# 18650_Test.net
KiCad netlist of a schematic drawn in EAGLE
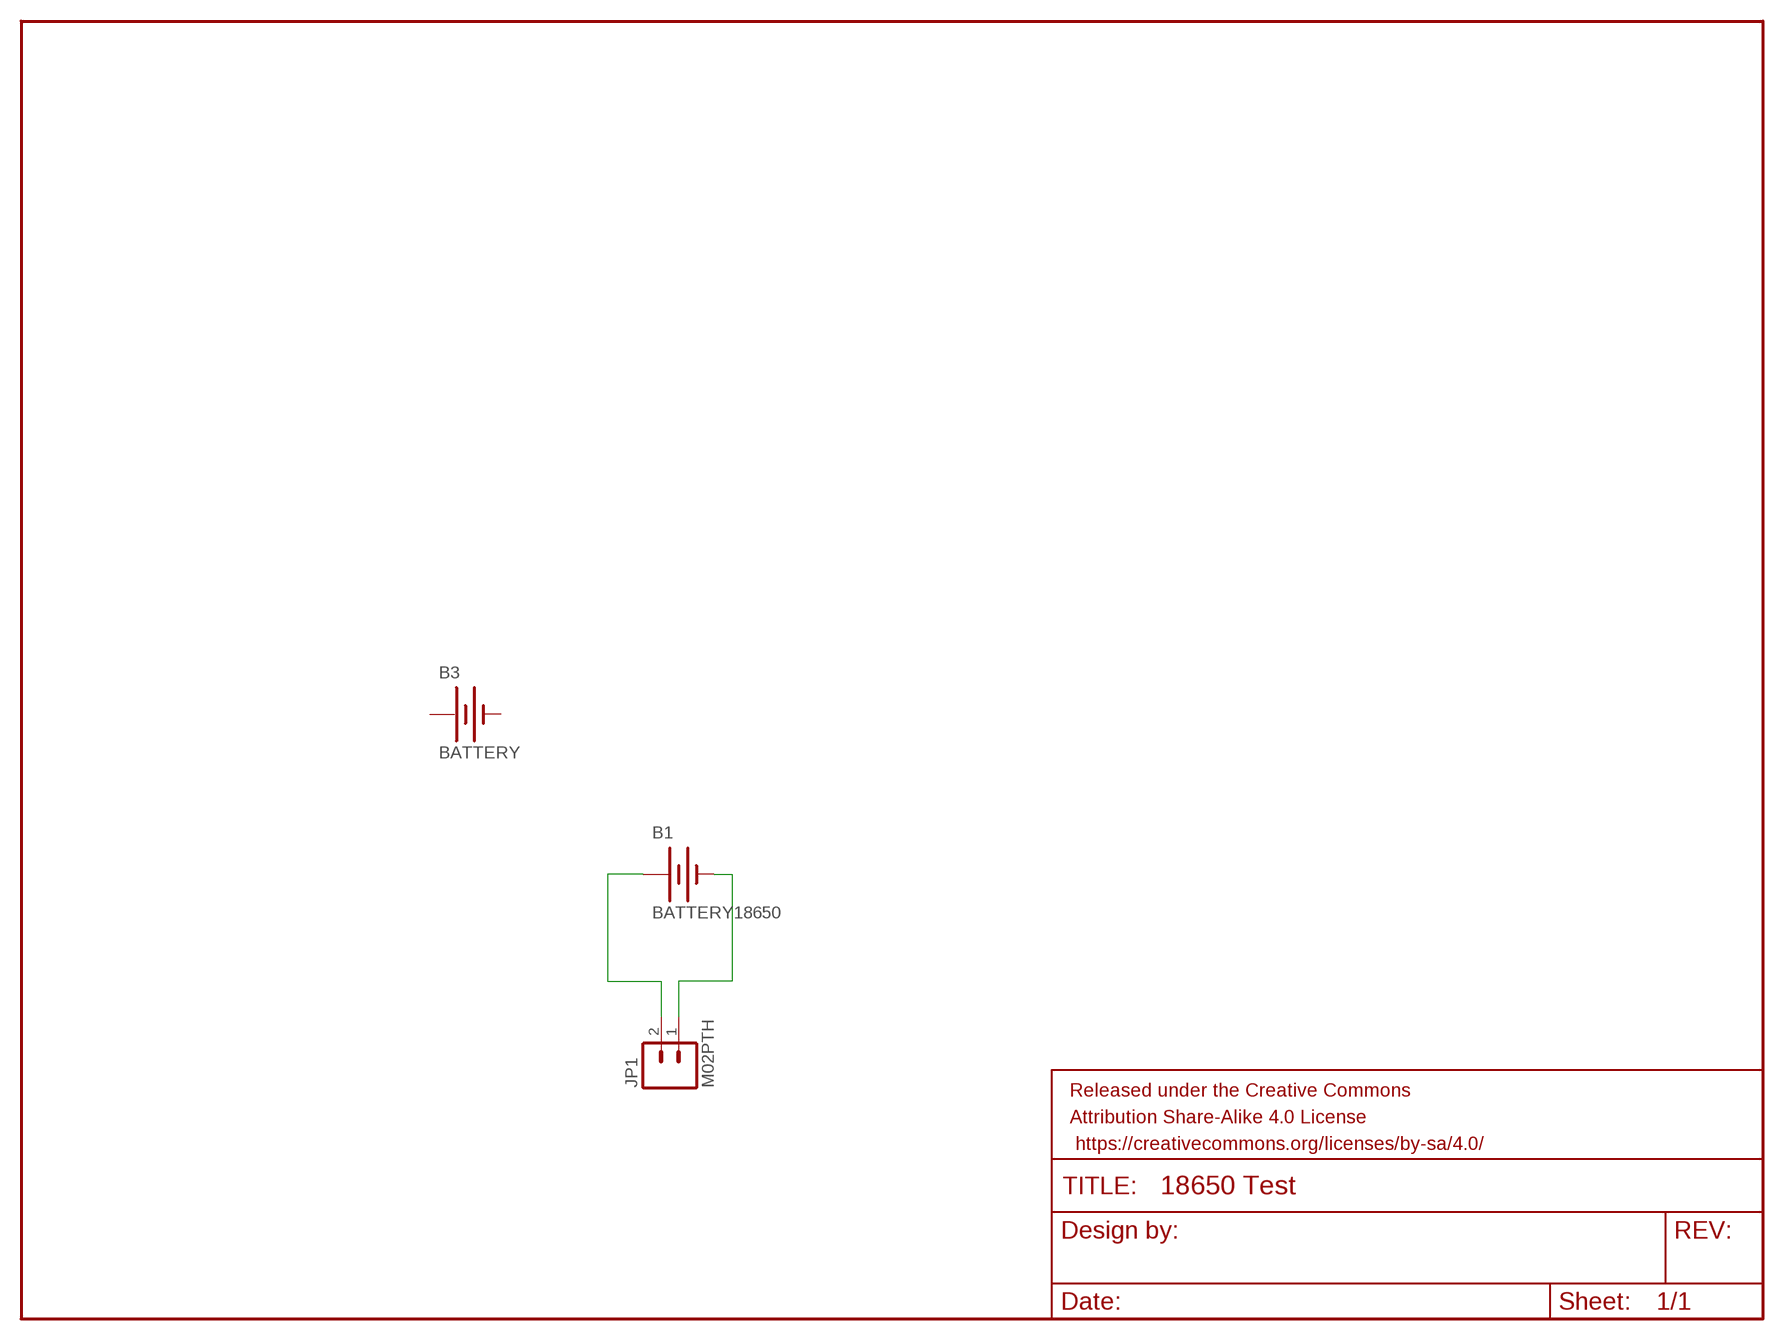
[diagram p0: schematic, sheet 1]

(export (version "E")
  (design (tool "Eeschema 10.0.6"))
  (components
    (comp (ref "B1")
      (value "BATTERY18650")
      (footprint "eagle-import:18650-HOLDER")
      (libsource (lib "eagle-import") (part "BATTERY18650"))
    )
    (comp (ref "B3")
      (value "BATTERY")
      (footprint "eagle-import:18650-TEST")
      (libsource (lib "eagle-import") (part "BATTERY"))
    )
    (comp (ref "FRAME1")
      (value "FRAME-LETTER")
      (footprint "eagle-import:CREATIVE_COMMONS")
      (libsource (lib "eagle-import") (part "FRAME-LETTER"))
    )
    (comp (ref "JP1")
      (value "M02PTH")
      (footprint "eagle-import:1X02")
      (libsource (lib "eagle-import") (part "M02PTH"))
    )
  )
  (nets
    (net (code "1") (name "/+") (class "Default")
      (node (ref "B3") (pin "PWR@4") (pinfunction "+_PWR@4") (pintype "power_in"))
    )
    (net (code "2") (name "/-") (class "Default")
      (node (ref "B3") (pin "PWR@3") (pinfunction "-_PWR@3") (pintype "power_in"))
    )
    (net (code "3") (name "Net-(B1-+)") (class "Default")
      (node (ref "B1") (pin "PWR@1") (pinfunction "+_PWR@1") (pintype "power_in"))
      (node (ref "JP1") (pin "2") (pinfunction "2_2") (pintype "passive"))
    )
    (net (code "4") (name "Net-(B1--)") (class "Default")
      (node (ref "B1") (pin "GND@1") (pinfunction "-_GND@1") (pintype "power_in"))
      (node (ref "JP1") (pin "1") (pinfunction "1_1") (pintype "passive"))
    )
  )
)
